# C128toSCART_SMT_V2_2021-01-28.net
KiCad netlist of a schematic drawn in EasyEDA
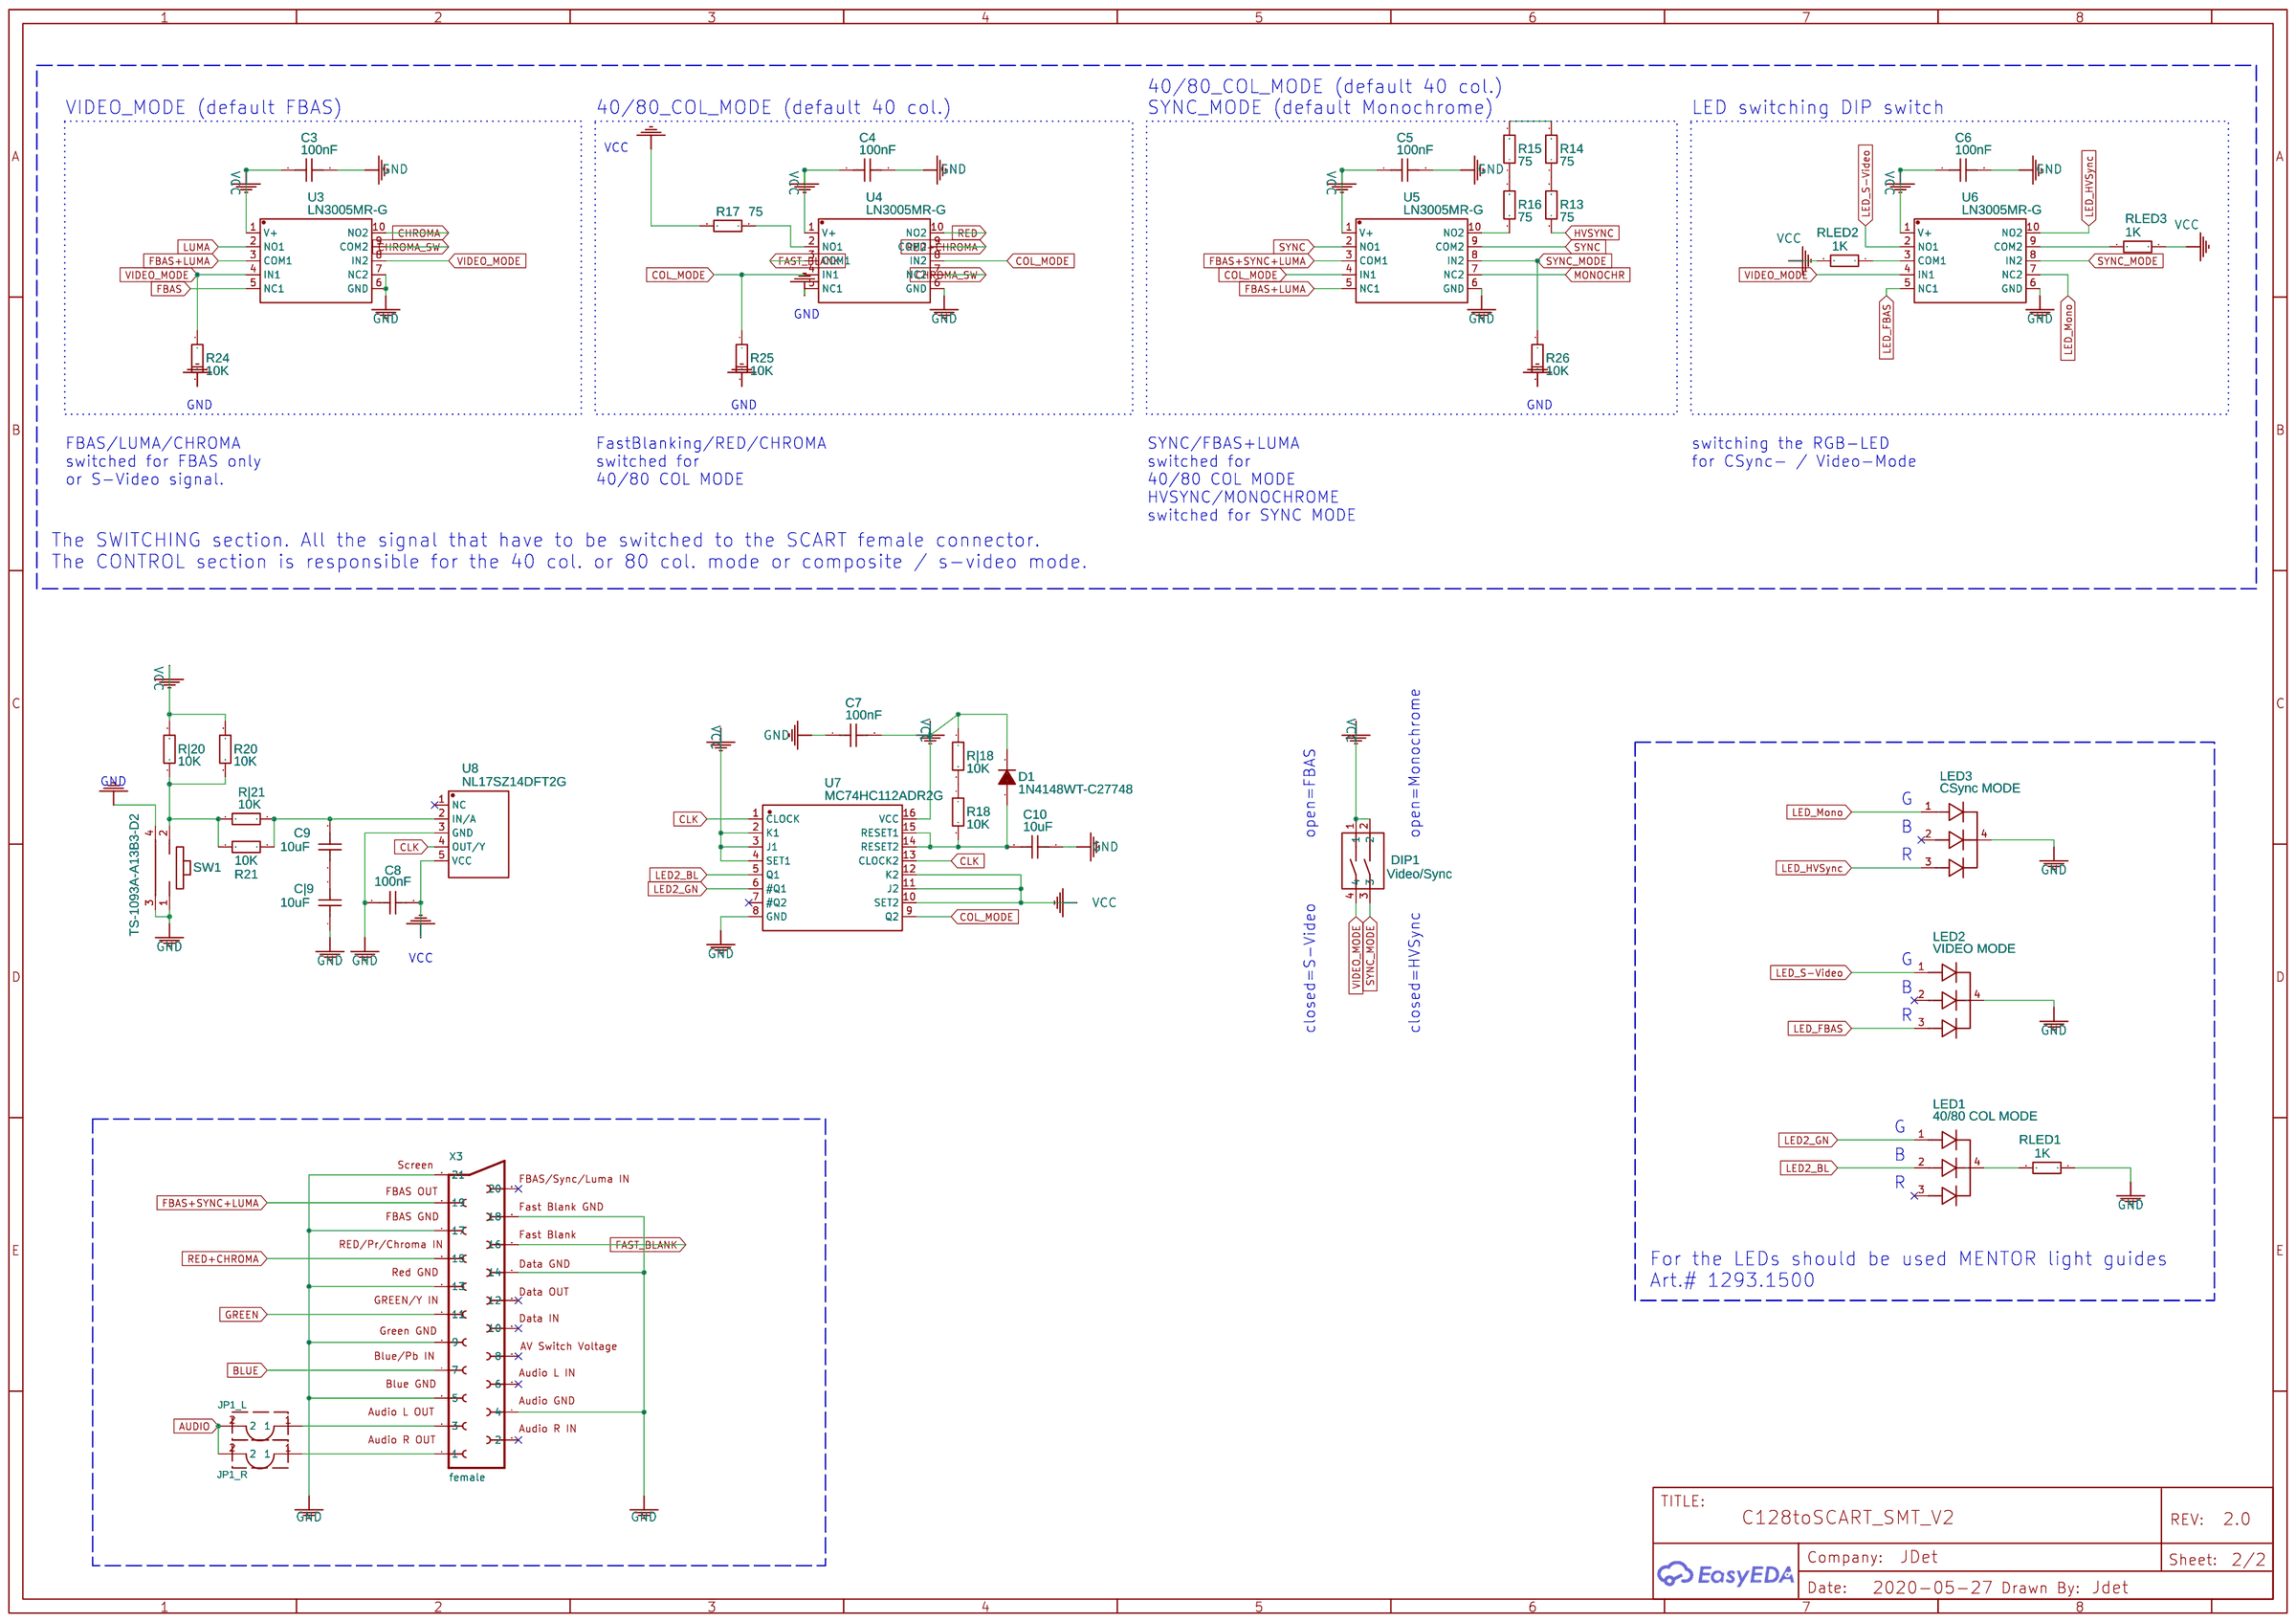
[diagram p0: C128toSCART_SMT_V2#2]
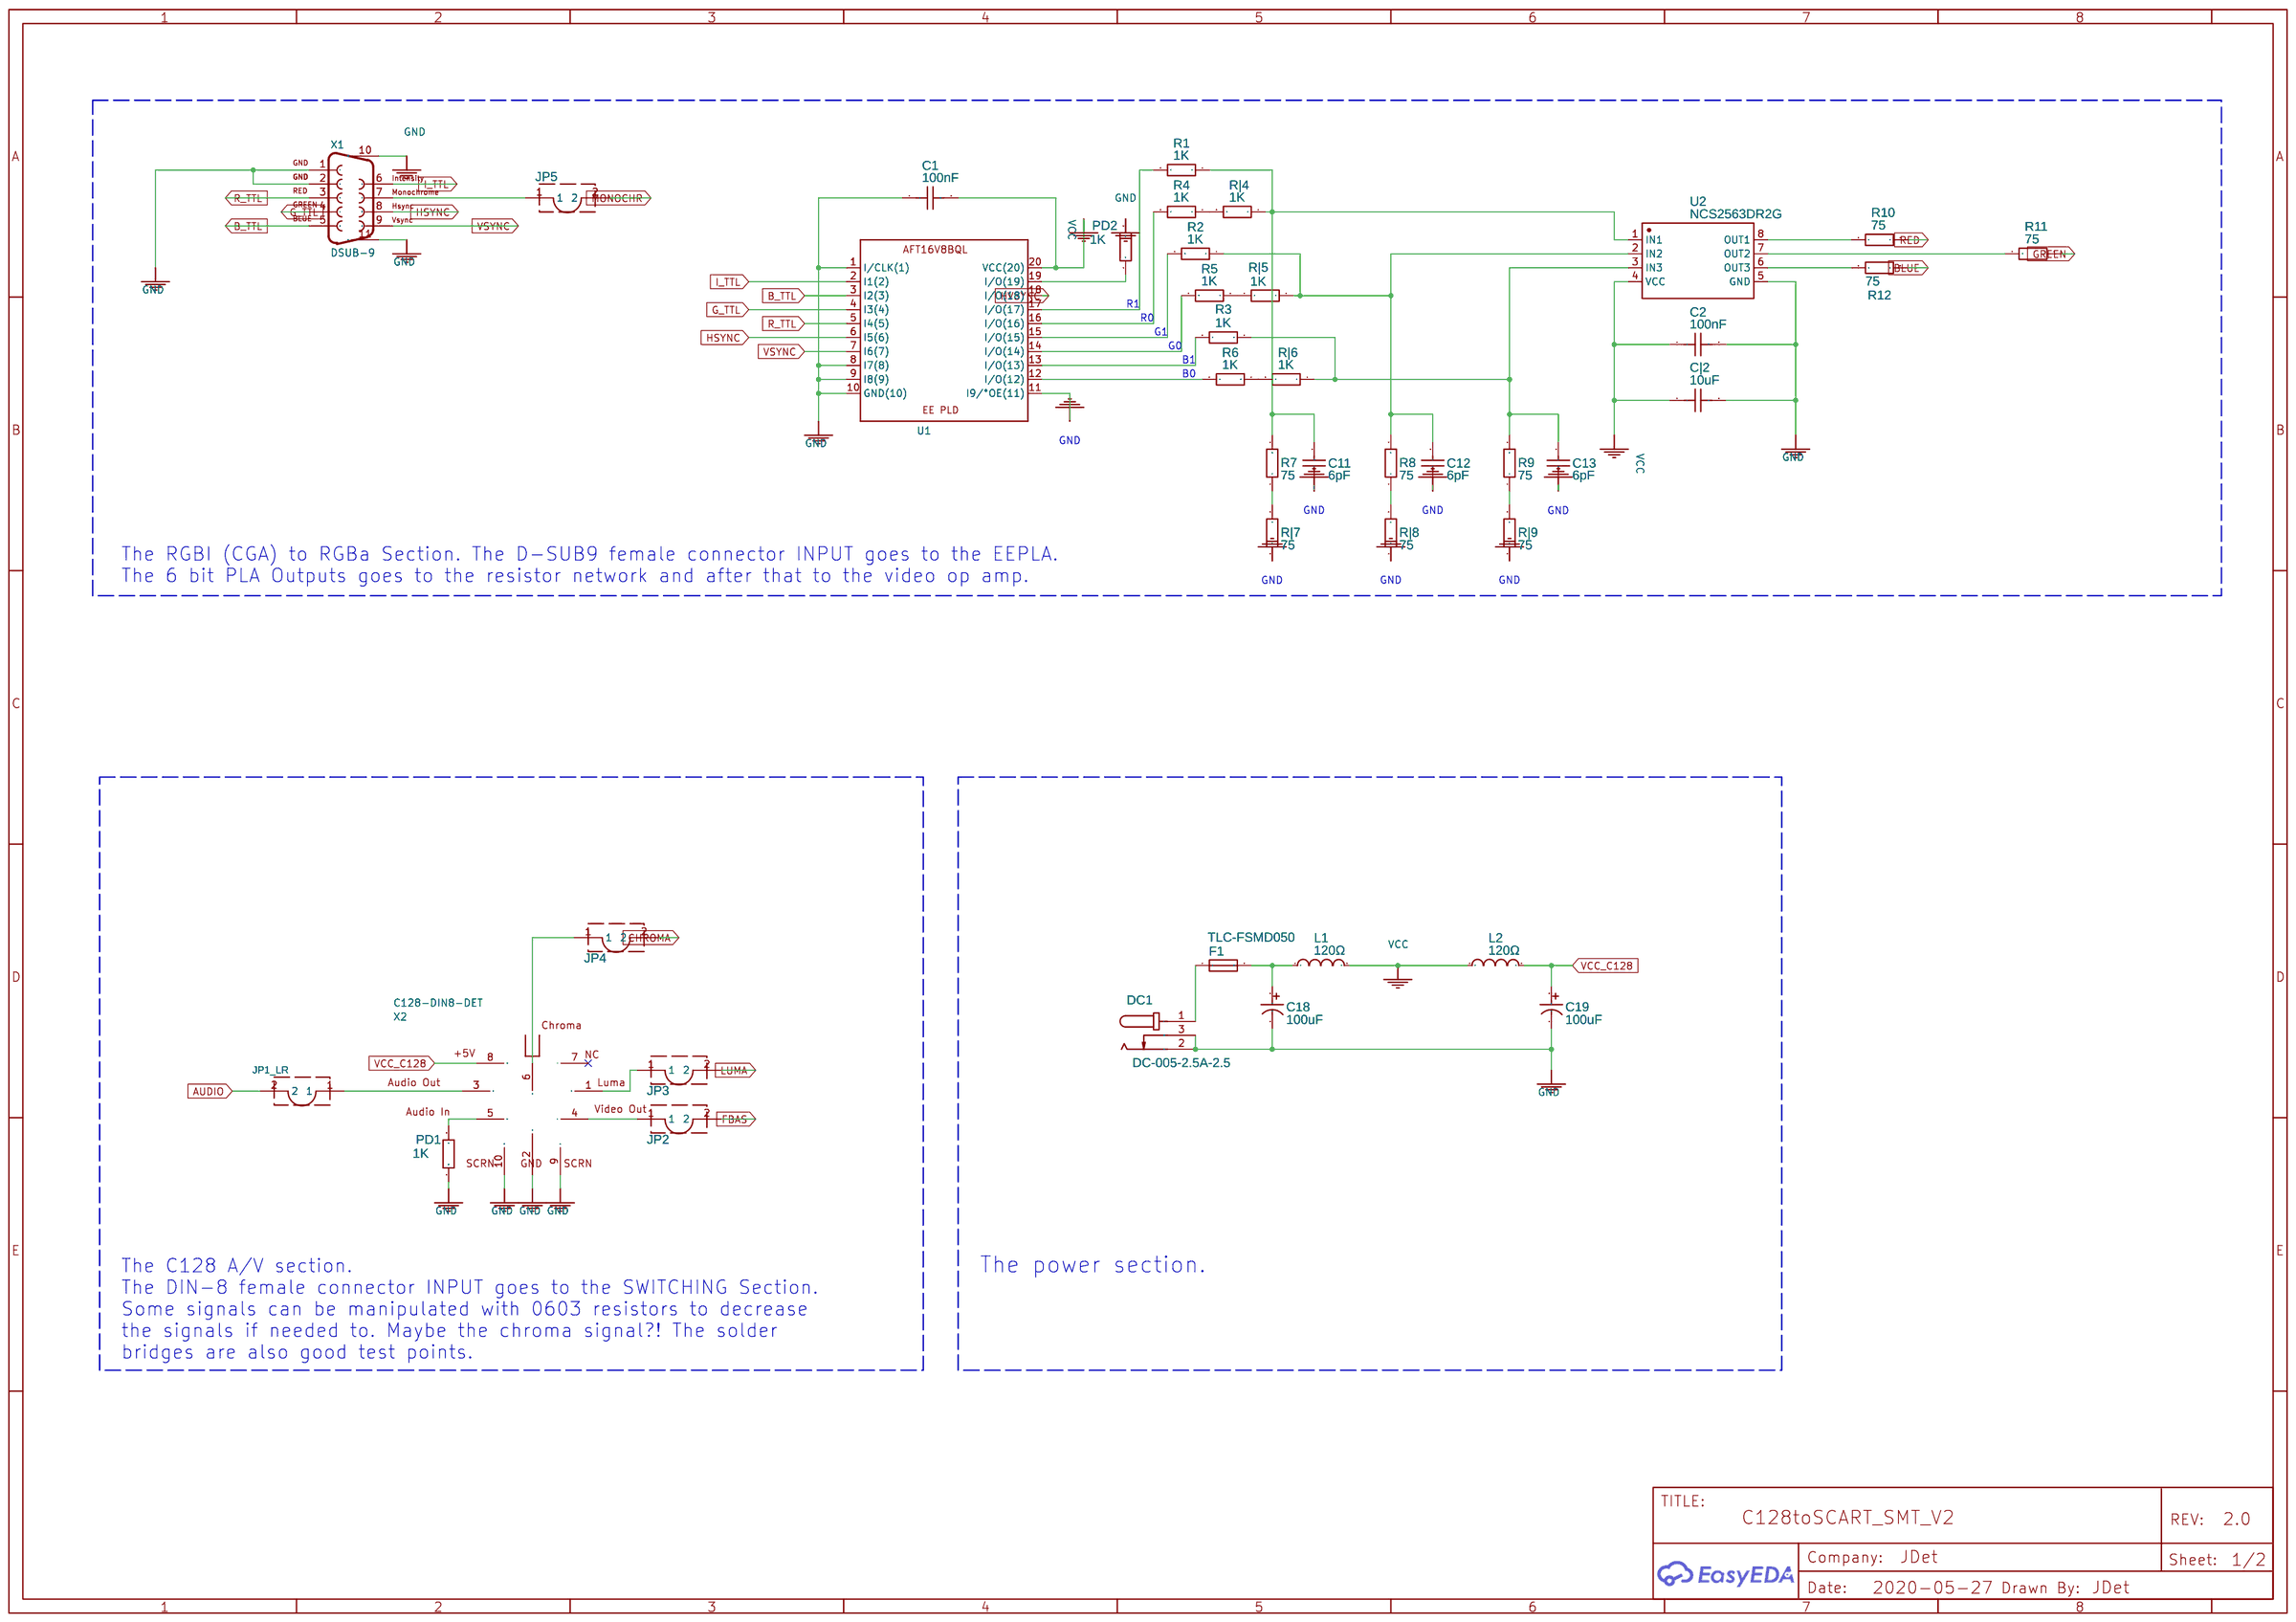
[diagram p1: C128toSCART_SMT_V2#1]

(export (version "E")
  (design (tool "Eeschema 10.0.6"))
  (components
    (comp (ref "C3")
      (value "100nF")
      (fields
        (field (name "BOM_Manufacturer Part") "CC0603KRX7R9BB104")
        (field (name "BOM_Supplier Part") "C14663")
      )
      (libsource (lib "") (part "CC0603KRX7R9BB104"))
    )
    (comp (ref "C4")
      (value "100nF")
      (fields
        (field (name "BOM_Manufacturer Part") "CC0603KRX7R9BB104")
        (field (name "BOM_Supplier Part") "C14663")
      )
      (libsource (lib "") (part "CC0603KRX7R9BB104"))
    )
    (comp (ref "C5")
      (value "100nF")
      (fields
        (field (name "BOM_Manufacturer Part") "CC0603KRX7R9BB104")
        (field (name "BOM_Supplier Part") "C14663")
      )
      (libsource (lib "") (part "CC0603KRX7R9BB104"))
    )
    (comp (ref "C6")
      (value "100nF")
      (fields
        (field (name "BOM_Manufacturer Part") "CC0603KRX7R9BB104")
        (field (name "BOM_Supplier Part") "C14663")
      )
      (libsource (lib "") (part "CC0603KRX7R9BB104"))
    )
    (comp (ref "C7")
      (value "100nF")
      (fields
        (field (name "BOM_Manufacturer Part") "CC0603KRX7R9BB104")
        (field (name "BOM_Supplier Part") "C14663")
      )
      (libsource (lib "") (part "CC0603KRX7R9BB104"))
    )
    (comp (ref "C8")
      (value "100nF")
      (fields
        (field (name "BOM_Manufacturer Part") "CC0603KRX7R9BB104")
        (field (name "BOM_Supplier Part") "C14663")
      )
      (libsource (lib "") (part "CC0603KRX7R9BB104"))
    )
    (comp (ref "C9")
      (value "10uF")
      (fields
        (field (name "BOM_Manufacturer Part") "CL10A106KP8NNNC")
        (field (name "BOM_Supplier Part") "C19702")
      )
      (libsource (lib "") (part "CL10A106KP8NNNC_1"))
    )
    (comp (ref "C10")
      (value "10uF")
      (fields
        (field (name "BOM_Manufacturer Part") "CL10A106KP8NNNC")
        (field (name "BOM_Supplier Part") "C19702")
      )
      (libsource (lib "") (part "CL10A106KP8NNNC_2"))
    )
    (comp (ref "C|9")
      (value "10uF")
      (fields
        (field (name "BOM_Manufacturer Part") "CL10A106KP8NNNC")
        (field (name "BOM_Supplier Part") "C19702")
      )
      (libsource (lib "") (part "CL10A106KP8NNNC"))
    )
    (comp (ref "D1")
      (value "1N4148WT-C27748")
      (fields (field (name "BOM_Manufacturer Part") "1N4148WT") (field (name "BOM_Supplier Part") "C27748"))
      (libsource (lib "") (part "1N4148WT-C27748"))
    )
    (comp (ref "DIP1")
      (value "Video/Sync")
      (fields (field (name "BOM_Manufacturer Part") "HAD-02HWA-R") (field (name "BOM_Supplier Part") "C4669"))
      (libsource (lib "") (part "HAD-02HWA-R"))
    )
    (comp (ref "JP1_L") (value "JUMPER_CLOSED") (libsource (lib "") (part "JUMPER_CLOSED_1")))
    (comp (ref "JP1_R") (value "JUMPER_CLOSED") (libsource (lib "") (part "JUMPER_CLOSED")))
    (comp (ref "LED1")
      (value "40/80 COL MODE")
      (fields
        (field (name "BOM_Manufacturer Part") "TJ-S1615SW6TGLCCSRGB-A5")
        (field (name "BOM_Supplier Part") "C273611")
      )
      (libsource (lib "") (part "TJ-S1615SW6TGLCCSRGB-A5"))
    )
    (comp (ref "LED2")
      (value "VIDEO MODE")
      (fields
        (field (name "BOM_Manufacturer Part") "TJ-S1615SW6TGLCCSRGB-A5")
        (field (name "BOM_Supplier Part") "C273611")
      )
      (libsource (lib "") (part "TJ-S1615SW6TGLCCSRGB-A5"))
    )
    (comp (ref "LED3")
      (value "CSync MODE")
      (fields
        (field (name "BOM_Manufacturer Part") "TJ-S1615SW6TGLCCSRGB-A5")
        (field (name "BOM_Supplier Part") "C273611")
      )
      (libsource (lib "") (part "TJ-S1615SW6TGLCCSRGB-A5"))
    )
    (comp (ref "R13")
      (value "75")
      (fields
        (field (name "BOM_Manufacturer Part") "TC0325B750JT5E")
        (field (name "BOM_Supplier Part") "C146567")
      )
      (libsource (lib "") (part "TC0325B750JT5E"))
    )
    (comp (ref "R14")
      (value "75")
      (fields
        (field (name "BOM_Manufacturer Part") "TC0325B750JT5E")
        (field (name "BOM_Supplier Part") "C146567")
      )
      (libsource (lib "") (part "TC0325B750JT5E"))
    )
    (comp (ref "R15")
      (value "75")
      (fields
        (field (name "BOM_Manufacturer Part") "TC0325B750JT5E")
        (field (name "BOM_Supplier Part") "C146567")
      )
      (libsource (lib "") (part "TC0325B750JT5E"))
    )
    (comp (ref "R16")
      (value "75")
      (fields
        (field (name "BOM_Manufacturer Part") "TC0325B750JT5E")
        (field (name "BOM_Supplier Part") "C146567")
      )
      (libsource (lib "") (part "TC0325B750JT5E"))
    )
    (comp (ref "R17")
      (value "75")
      (fields
        (field (name "BOM_Manufacturer Part") "TC0325B750JT5E")
        (field (name "BOM_Supplier Part") "C146567")
      )
      (libsource (lib "") (part "TC0325B750JT5E_1"))
    )
    (comp (ref "R18")
      (value "10K")
      (fields
        (field (name "BOM_Manufacturer Part") "TC0310B1002T5E")
        (field (name "BOM_Supplier Part") "C190321")
      )
      (libsource (lib "") (part "TC0310B1002T5E_1"))
    )
    (comp (ref "R20")
      (value "10K")
      (fields
        (field (name "BOM_Manufacturer Part") "TC0310B1002T5E")
        (field (name "BOM_Supplier Part") "C190321")
      )
      (libsource (lib "") (part "TC0310B1002T5E_2"))
    )
    (comp (ref "R21")
      (value "10K")
      (fields
        (field (name "BOM_Manufacturer Part") "TC0310B1002T5E")
        (field (name "BOM_Supplier Part") "C190321")
      )
      (libsource (lib "") (part "TC0310B1002T5E"))
    )
    (comp (ref "R24")
      (value "10K")
      (fields
        (field (name "BOM_Manufacturer Part") "TC0310B1002T5E")
        (field (name "BOM_Supplier Part") "C190321")
      )
      (libsource (lib "") (part "TC0310B1002T5E_1"))
    )
    (comp (ref "R25")
      (value "10K")
      (fields
        (field (name "BOM_Manufacturer Part") "TC0310B1002T5E")
        (field (name "BOM_Supplier Part") "C190321")
      )
      (libsource (lib "") (part "TC0310B1002T5E_1"))
    )
    (comp (ref "R26")
      (value "10K")
      (fields
        (field (name "BOM_Manufacturer Part") "TC0310B1002T5E")
        (field (name "BOM_Supplier Part") "C190321")
      )
      (libsource (lib "") (part "TC0310B1002T5E_1"))
    )
    (comp (ref "RLED1")
      (value "1K")
      (fields
        (field (name "BOM_Manufacturer Part") "TC0325F1001T5E")
        (field (name "BOM_Supplier Part") "C128783")
      )
      (libsource (lib "") (part "TC0325F1001T5E"))
    )
    (comp (ref "RLED2")
      (value "1K")
      (fields
        (field (name "BOM_Manufacturer Part") "TC0325F1001T5E")
        (field (name "BOM_Supplier Part") "C128783")
      )
      (libsource (lib "") (part "TC0325F1001T5E"))
    )
    (comp (ref "RLED3")
      (value "1K")
      (fields
        (field (name "BOM_Manufacturer Part") "TC0325F1001T5E")
        (field (name "BOM_Supplier Part") "C128783")
      )
      (libsource (lib "") (part "TC0325F1001T5E"))
    )
    (comp (ref "R|18")
      (value "10K")
      (fields
        (field (name "BOM_Manufacturer Part") "TC0310B1002T5E")
        (field (name "BOM_Supplier Part") "C190321")
      )
      (libsource (lib "") (part "TC0310B1002T5E_5"))
    )
    (comp (ref "R|20")
      (value "10K")
      (fields
        (field (name "BOM_Manufacturer Part") "TC0310B1002T5E")
        (field (name "BOM_Supplier Part") "C190321")
      )
      (libsource (lib "") (part "TC0310B1002T5E_3"))
    )
    (comp (ref "R|21")
      (value "10K")
      (fields
        (field (name "BOM_Manufacturer Part") "TC0310B1002T5E")
        (field (name "BOM_Supplier Part") "C190321")
      )
      (libsource (lib "") (part "TC0310B1002T5E_4"))
    )
    (comp (ref "SW1")
      (value "TS-1093A-A13B3-D2")
      (fields (field (name "BOM_Supplier Part") "C499320"))
      (libsource (lib "") (part "TS-1093A-A13B3-D2"))
    )
    (comp (ref "U3")
      (value "LN3005MR-G")
      (fields (field (name "BOM_Supplier Part") "C236380"))
      (libsource (lib "") (part "LN3005MR-G"))
    )
    (comp (ref "U4")
      (value "LN3005MR-G")
      (fields (field (name "BOM_Supplier Part") "C236380"))
      (libsource (lib "") (part "LN3005MR-G"))
    )
    (comp (ref "U5")
      (value "LN3005MR-G")
      (fields (field (name "BOM_Supplier Part") "C236380"))
      (libsource (lib "") (part "LN3005MR-G"))
    )
    (comp (ref "U6")
      (value "LN3005MR-G")
      (fields (field (name "BOM_Supplier Part") "C236380"))
      (libsource (lib "") (part "LN3005MR-G"))
    )
    (comp (ref "U7")
      (value "MC74HC112ADR2G")
      (fields (field (name "BOM_Supplier Part") "C233600"))
      (libsource (lib "") (part "MC74HC112ADR2G"))
    )
    (comp (ref "U8")
      (value "NL17SZ14DFT2G")
      (fields (field (name "BOM_Supplier Part") "C113256"))
      (libsource (lib "") (part "NL17SZ14DFT2G"))
    )
    (comp (ref "X3") (value "female") (libsource (lib "") (part "Unknown_325_-200")))
    (comp (ref "C1")
      (value "100nF")
      (fields
        (field (name "BOM_Manufacturer Part") "CC0603KRX7R9BB104")
        (field (name "BOM_Supplier Part") "C14663")
      )
      (libsource (lib "") (part "CC0603KRX7R9BB104"))
    )
    (comp (ref "C2")
      (value "100nF")
      (fields
        (field (name "BOM_Manufacturer Part") "CC0603KRX7R9BB104")
        (field (name "BOM_Supplier Part") "C14663")
      )
      (libsource (lib "") (part "CC0603KRX7R9BB104"))
    )
    (comp (ref "C11")
      (value "6pF")
      (fields
        (field (name "BOM_Manufacturer Part") "0603CG6R0C500NT")
        (field (name "BOM_Supplier Part") "C37474")
      )
      (libsource (lib "") (part "0603CG6R0C500NT"))
    )
    (comp (ref "C12")
      (value "6pF")
      (fields
        (field (name "BOM_Manufacturer Part") "0603CG6R0C500NT")
        (field (name "BOM_Supplier Part") "C37474")
      )
      (libsource (lib "") (part "0603CG6R0C500NT"))
    )
    (comp (ref "C13")
      (value "6pF")
      (fields
        (field (name "BOM_Manufacturer Part") "0603CG6R0C500NT")
        (field (name "BOM_Supplier Part") "C37474")
      )
      (libsource (lib "") (part "0603CG6R0C500NT"))
    )
    (comp (ref "C18")
      (value "100uF")
      (fields
        (field (name "BOM_Manufacturer Part") "VZS101M1ATR-0506")
        (field (name "BOM_Supplier Part") "C140924")
      )
      (libsource (lib "") (part "VZS101M1ATR-0506"))
    )
    (comp (ref "C19")
      (value "100uF")
      (fields
        (field (name "BOM_Manufacturer Part") "VZS101M1ATR-0506")
        (field (name "BOM_Supplier Part") "C140924")
      )
      (libsource (lib "") (part "VZS101M1ATR-0506"))
    )
    (comp (ref "C|2")
      (value "10uF")
      (fields
        (field (name "BOM_Manufacturer Part") "CL10A106KP8NNNC")
        (field (name "BOM_Supplier Part") "C19702")
      )
      (libsource (lib "") (part "CL10A106KP8NNNC"))
    )
    (comp (ref "DC1")
      (value "DC-005-2.5A-2.5")
      (fields (field (name "BOM_Supplier Part") "C319098"))
      (libsource (lib "") (part "DC-005-2.5A-2.5"))
    )
    (comp (ref "F1")
      (value "TLC-FSMD050")
      (fields (field (name "BOM_Supplier Part") "C261937"))
      (libsource (lib "") (part "TLC-FSMD050"))
    )
    (comp (ref "JP1_LR") (value "JUMPER_CLOSED") (libsource (lib "") (part "JUMPER_CLOSED_1")))
    (comp (ref "JP2") (value "JUMPER_CLOSED") (libsource (lib "") (part "JUMPER_CLOSED")))
    (comp (ref "JP3") (value "JUMPER_CLOSED") (libsource (lib "") (part "JUMPER_CLOSED")))
    (comp (ref "JP4") (value "JUMPER_CLOSED") (libsource (lib "") (part "JUMPER_CLOSED")))
    (comp (ref "JP5") (value "JUMPER_CLOSED") (libsource (lib "") (part "JUMPER_CLOSED")))
    (comp (ref "L1")
      (value "120Ω")
      (fields
        (field (name "BOM_Manufacturer Part") "GZ1608D121TF")
        (field (name "BOM_Supplier Part") "C18527")
      )
      (libsource (lib "") (part "GZ1608D121TF"))
    )
    (comp (ref "L2")
      (value "120Ω")
      (fields
        (field (name "BOM_Manufacturer Part") "GZ1608D121TF")
        (field (name "BOM_Supplier Part") "C18527")
      )
      (libsource (lib "") (part "GZ1608D121TF_1"))
    )
    (comp (ref "PD1")
      (value "1K")
      (fields
        (field (name "BOM_Manufacturer Part") "TC0325F1001T5E")
        (field (name "BOM_Supplier Part") "C128783")
      )
      (libsource (lib "") (part "TC0325F1001T5E"))
    )
    (comp (ref "PD2")
      (value "1K")
      (fields
        (field (name "BOM_Manufacturer Part") "TC0325F1001T5E")
        (field (name "BOM_Supplier Part") "C128783")
      )
      (libsource (lib "") (part "TC0325F1001T5E"))
    )
    (comp (ref "R1")
      (value "1K")
      (fields
        (field (name "BOM_Manufacturer Part") "TC0325F1001T5E")
        (field (name "BOM_Supplier Part") "C128783")
      )
      (libsource (lib "") (part "TC0325F1001T5E_1"))
    )
    (comp (ref "R2")
      (value "1K")
      (fields
        (field (name "BOM_Manufacturer Part") "TC0325F1001T5E")
        (field (name "BOM_Supplier Part") "C128783")
      )
      (libsource (lib "") (part "TC0325F1001T5E_1"))
    )
    (comp (ref "R3")
      (value "1K")
      (fields
        (field (name "BOM_Manufacturer Part") "TC0325F1001T5E")
        (field (name "BOM_Supplier Part") "C128783")
      )
      (libsource (lib "") (part "TC0325F1001T5E_1"))
    )
    (comp (ref "R4")
      (value "1K")
      (fields
        (field (name "BOM_Manufacturer Part") "TC0325F1001T5E")
        (field (name "BOM_Supplier Part") "C128783")
      )
      (libsource (lib "") (part "TC0325F1001T5E_1"))
    )
    (comp (ref "R5")
      (value "1K")
      (fields
        (field (name "BOM_Manufacturer Part") "TC0325F1001T5E")
        (field (name "BOM_Supplier Part") "C128783")
      )
      (libsource (lib "") (part "TC0325F1001T5E_1"))
    )
    (comp (ref "R6")
      (value "1K")
      (fields
        (field (name "BOM_Manufacturer Part") "TC0325F1001T5E")
        (field (name "BOM_Supplier Part") "C128783")
      )
      (libsource (lib "") (part "TC0325F1001T5E_1"))
    )
    (comp (ref "R7")
      (value "75")
      (fields
        (field (name "BOM_Manufacturer Part") "TC0325B750JT5E")
        (field (name "BOM_Supplier Part") "C146567")
      )
      (libsource (lib "") (part "TC0325B750JT5E"))
    )
    (comp (ref "R8")
      (value "75")
      (fields
        (field (name "BOM_Manufacturer Part") "TC0325B750JT5E")
        (field (name "BOM_Supplier Part") "C146567")
      )
      (libsource (lib "") (part "TC0325B750JT5E"))
    )
    (comp (ref "R9")
      (value "75")
      (fields
        (field (name "BOM_Manufacturer Part") "TC0325B750JT5E")
        (field (name "BOM_Supplier Part") "C146567")
      )
      (libsource (lib "") (part "TC0325B750JT5E"))
    )
    (comp (ref "R10")
      (value "75")
      (fields
        (field (name "BOM_Manufacturer Part") "TC0325B750JT5E")
        (field (name "BOM_Supplier Part") "C146567")
      )
      (libsource (lib "") (part "TC0325B750JT5E_2"))
    )
    (comp (ref "R11")
      (value "75")
      (fields
        (field (name "BOM_Manufacturer Part") "TC0325B750JT5E")
        (field (name "BOM_Supplier Part") "C146567")
      )
      (libsource (lib "") (part "TC0325B750JT5E_2"))
    )
    (comp (ref "R12")
      (value "75")
      (fields
        (field (name "BOM_Manufacturer Part") "TC0325B750JT5E")
        (field (name "BOM_Supplier Part") "C146567")
      )
      (libsource (lib "") (part "TC0325B750JT5E_2"))
    )
    (comp (ref "R|4")
      (value "1K")
      (fields
        (field (name "BOM_Manufacturer Part") "TC0325F1001T5E")
        (field (name "BOM_Supplier Part") "C128783")
      )
      (libsource (lib "") (part "TC0325F1001T5E_2"))
    )
    (comp (ref "R|5")
      (value "1K")
      (fields
        (field (name "BOM_Manufacturer Part") "TC0325F1001T5E")
        (field (name "BOM_Supplier Part") "C128783")
      )
      (libsource (lib "") (part "TC0325F1001T5E_2"))
    )
    (comp (ref "R|6")
      (value "1K")
      (fields
        (field (name "BOM_Manufacturer Part") "TC0325F1001T5E")
        (field (name "BOM_Supplier Part") "C128783")
      )
      (libsource (lib "") (part "TC0325F1001T5E_2"))
    )
    (comp (ref "R|7")
      (value "75")
      (fields
        (field (name "BOM_Manufacturer Part") "TC0325B750JT5E")
        (field (name "BOM_Supplier Part") "C146567")
      )
      (libsource (lib "") (part "TC0325B750JT5E_1"))
    )
    (comp (ref "R|8")
      (value "75")
      (fields
        (field (name "BOM_Manufacturer Part") "TC0325B750JT5E")
        (field (name "BOM_Supplier Part") "C146567")
      )
      (libsource (lib "") (part "TC0325B750JT5E_1"))
    )
    (comp (ref "R|9")
      (value "75")
      (fields
        (field (name "BOM_Manufacturer Part") "TC0325B750JT5E")
        (field (name "BOM_Supplier Part") "C146567")
      )
      (libsource (lib "") (part "TC0325B750JT5E_1"))
    )
    (comp (ref "U1") (value "ATF16V8BQ") (libsource (lib "") (part "Unknown_650_-880")))
    (comp (ref "U2")
      (value "NCS2563DR2G")
      (fields (field (name "BOM_Supplier Part") "C97773"))
      (libsource (lib "") (part "NCS2563DR2G"))
    )
    (comp (ref "X1") (value "DSUB-9") (libsource (lib "") (part "Unknown_235_-1000")))
    (comp (ref "X2") (value "C128-DIN8-DET") (libsource (lib "") (part "Unknown_365_-360")))
  )
  (nets
    (net (code "1") (name "AUDIO") (class "Default")
      (node (ref "JP1_L") (pin "2") (pinfunction "2_2") (pintype "unspecified"))
      (node (ref "JP1_LR") (pin "2") (pinfunction "2_2") (pintype "unspecified"))
      (node (ref "JP1_R") (pin "2") (pinfunction "2_2") (pintype "unspecified"))
    )
    (net (code "2") (name "BLUE") (class "Default")
      (node (ref "R12") (pin "1") (pinfunction "1_1") (pintype "input"))
      (node (ref "X3") (pin "7") (pinfunction "7_7") (pintype "bidirectional"))
    )
    (net (code "3") (name "B_TTL") (class "Default")
      (node (ref "U1") (pin "3") (pinfunction "I2(3)_3") (pintype "bidirectional"))
      (node (ref "X1") (pin "5") (pinfunction "5_5") (pintype "bidirectional"))
    )
    (net (code "4") (name "CHROMA") (class "Default")
      (node (ref "JP4") (pin "2") (pinfunction "2_2") (pintype "unspecified"))
      (node (ref "U3") (pin "10") (pinfunction "NO2_10") (pintype "unspecified"))
    )
    (net (code "5") (name "CHROMA_SW") (class "Default")
      (node (ref "U3") (pin "9") (pinfunction "COM2_9") (pintype "unspecified"))
      (node (ref "U4") (pin "7") (pinfunction "NC2_7") (pintype "unspecified"))
    )
    (net (code "6") (name "CLK") (class "Default")
      (node (ref "U7") (pin "1") (pinfunction "CLOCK_1") (pintype "unspecified"))
      (node (ref "U7") (pin "13") (pinfunction "CLOCK2_13") (pintype "unspecified"))
      (node (ref "U8") (pin "4") (pinfunction "OUT/Y_4") (pintype "unspecified"))
    )
    (net (code "7") (name "COL_MODE") (class "Default")
      (node (ref "R25") (pin "1") (pinfunction "1_1") (pintype "unspecified"))
      (node (ref "U4") (pin "4") (pinfunction "IN1_4") (pintype "unspecified"))
      (node (ref "U4") (pin "8") (pinfunction "IN2_8") (pintype "unspecified"))
      (node (ref "U5") (pin "4") (pinfunction "IN1_4") (pintype "unspecified"))
      (node (ref "U7") (pin "9") (pinfunction "Q2_9") (pintype "unspecified"))
    )
    (net (code "8") (name "FAST_BLANK") (class "Default")
      (node (ref "U4") (pin "3") (pinfunction "COM1_3") (pintype "unspecified"))
      (node (ref "X3") (pin "16") (pinfunction "16_16") (pintype "bidirectional"))
    )
    (net (code "9") (name "FBAS") (class "Default")
      (node (ref "JP2") (pin "2") (pinfunction "2_2") (pintype "unspecified"))
      (node (ref "U3") (pin "5") (pinfunction "NC1_5") (pintype "unspecified"))
    )
    (net (code "10") (name "FBAS+LUMA") (class "Default")
      (node (ref "U3") (pin "3") (pinfunction "COM1_3") (pintype "unspecified"))
      (node (ref "U5") (pin "5") (pinfunction "NC1_5") (pintype "unspecified"))
    )
    (net (code "11") (name "FBAS+SYNC+LUMA") (class "Default")
      (node (ref "U5") (pin "3") (pinfunction "COM1_3") (pintype "unspecified"))
      (node (ref "X3") (pin "19") (pinfunction "19_19") (pintype "bidirectional"))
    )
    (net (code "12") (name "GND") (class "Default")
      (node (ref "C1") (pin "1") (pinfunction "1_1") (pintype "unspecified"))
      (node (ref "C10") (pin "1") (pinfunction "1_1") (pintype "unspecified"))
      (node (ref "C11") (pin "1") (pinfunction "1_1") (pintype "input"))
      (node (ref "C12") (pin "1") (pinfunction "1_1") (pintype "input"))
      (node (ref "C13") (pin "1") (pinfunction "1_1") (pintype "input"))
      (node (ref "C18") (pin "2") (pinfunction "2_2") (pintype "input"))
      (node (ref "C19") (pin "2") (pinfunction "2_2") (pintype "input"))
      (node (ref "C2") (pin "2") (pinfunction "2_2") (pintype "unspecified"))
      (node (ref "C3") (pin "2") (pinfunction "2_2") (pintype "unspecified"))
      (node (ref "C4") (pin "2") (pinfunction "2_2") (pintype "unspecified"))
      (node (ref "C5") (pin "2") (pinfunction "2_2") (pintype "unspecified"))
      (node (ref "C6") (pin "2") (pinfunction "2_2") (pintype "unspecified"))
      (node (ref "C7") (pin "1") (pinfunction "1_1") (pintype "unspecified"))
      (node (ref "C8") (pin "1") (pinfunction "1_1") (pintype "unspecified"))
      (node (ref "C|2") (pin "2") (pinfunction "2_2") (pintype "unspecified"))
      (node (ref "C|9") (pin "1") (pinfunction "1_1") (pintype "unspecified"))
      (node (ref "DC1") (pin "2") (pinfunction "2_2") (pintype "unspecified"))
      (node (ref "DC1") (pin "3") (pinfunction "3_3") (pintype "unspecified"))
      (node (ref "LED2") (pin "4") (pinfunction "4_4") (pintype "unspecified"))
      (node (ref "LED3") (pin "4") (pinfunction "4_4") (pintype "unspecified"))
      (node (ref "PD1") (pin "1") (pinfunction "1_1") (pintype "unspecified"))
      (node (ref "PD2") (pin "2") (pinfunction "2_2") (pintype "unspecified"))
      (node (ref "R24") (pin "2") (pinfunction "2_2") (pintype "unspecified"))
      (node (ref "R25") (pin "2") (pinfunction "2_2") (pintype "unspecified"))
      (node (ref "R26") (pin "2") (pinfunction "2_2") (pintype "unspecified"))
      (node (ref "RLED1") (pin "1") (pinfunction "1_1") (pintype "unspecified"))
      (node (ref "R|7") (pin "1") (pinfunction "1_1") (pintype "input"))
      (node (ref "R|8") (pin "1") (pinfunction "1_1") (pintype "input"))
      (node (ref "R|9") (pin "1") (pinfunction "1_1") (pintype "input"))
      (node (ref "SW1") (pin "1") (pinfunction "1_1") (pintype "unspecified"))
      (node (ref "SW1") (pin "3") (pinfunction "3_3") (pintype "unspecified"))
      (node (ref "SW1") (pin "4") (pinfunction "4_4") (pintype "unspecified"))
      (node (ref "U1") (pin "1") (pinfunction "I/CLK(1)_1") (pintype "bidirectional"))
      (node (ref "U1") (pin "10") (pinfunction "GND(10)_10") (pintype "bidirectional"))
      (node (ref "U1") (pin "11") (pinfunction "I9/°OE(11)_11") (pintype "bidirectional"))
      (node (ref "U1") (pin "8") (pinfunction "I7(8)_8") (pintype "bidirectional"))
      (node (ref "U1") (pin "9") (pinfunction "I8(9)_9") (pintype "bidirectional"))
      (node (ref "U2") (pin "5") (pinfunction "GND_5") (pintype "unspecified"))
      (node (ref "U3") (pin "6") (pinfunction "GND_6") (pintype "unspecified"))
      (node (ref "U3") (pin "7") (pinfunction "NC2_7") (pintype "unspecified"))
      (node (ref "U4") (pin "5") (pinfunction "NC1_5") (pintype "unspecified"))
      (node (ref "U4") (pin "6") (pinfunction "GND_6") (pintype "unspecified"))
      (node (ref "U5") (pin "6") (pinfunction "GND_6") (pintype "unspecified"))
      (node (ref "U6") (pin "6") (pinfunction "GND_6") (pintype "unspecified"))
      (node (ref "U7") (pin "8") (pinfunction "GND_8") (pintype "unspecified"))
      (node (ref "U8") (pin "3") (pinfunction "GND_3") (pintype "unspecified"))
      (node (ref "X1") (pin "1") (pinfunction "1_1") (pintype "bidirectional"))
      (node (ref "X1") (pin "10") (pinfunction "10_10") (pintype "bidirectional"))
      (node (ref "X1") (pin "11") (pinfunction "11_11") (pintype "bidirectional"))
      (node (ref "X1") (pin "2") (pinfunction "2_2") (pintype "bidirectional"))
      (node (ref "X2") (pin "10") (pinfunction "10_10") (pintype "bidirectional"))
      (node (ref "X2") (pin "2") (pinfunction "2_2") (pintype "bidirectional"))
      (node (ref "X2") (pin "9") (pinfunction "9_9") (pintype "bidirectional"))
      (node (ref "X3") (pin "13") (pinfunction "13_13") (pintype "bidirectional"))
      (node (ref "X3") (pin "14") (pinfunction "14_14") (pintype "bidirectional"))
      (node (ref "X3") (pin "17") (pinfunction "17_17") (pintype "bidirectional"))
      (node (ref "X3") (pin "18") (pinfunction "18_18") (pintype "bidirectional"))
      (node (ref "X3") (pin "21") (pinfunction "21_21") (pintype "bidirectional"))
      (node (ref "X3") (pin "4") (pinfunction "4_4") (pintype "bidirectional"))
      (node (ref "X3") (pin "5") (pinfunction "5_5") (pintype "bidirectional"))
      (node (ref "X3") (pin "9") (pinfunction "9_9") (pintype "bidirectional"))
    )
    (net (code "13") (name "GREEN") (class "Default")
      (node (ref "R11") (pin "1") (pinfunction "1_1") (pintype "input"))
      (node (ref "X3") (pin "11") (pinfunction "11_11") (pintype "bidirectional"))
    )
    (net (code "14") (name "G_TTL") (class "Default")
      (node (ref "U1") (pin "4") (pinfunction "I3(4)_4") (pintype "bidirectional"))
      (node (ref "X1") (pin "4") (pinfunction "4_4") (pintype "bidirectional"))
    )
    (net (code "15") (name "HSYNC") (class "Default")
      (node (ref "U1") (pin "6") (pinfunction "I5(6)_6") (pintype "bidirectional"))
      (node (ref "X1") (pin "8") (pinfunction "8_8") (pintype "bidirectional"))
    )
    (net (code "16") (name "HVSYNC") (class "Default")
      (node (ref "R13") (pin "1") (pinfunction "1_1") (pintype "input"))
      (node (ref "U1") (pin "18") (pinfunction "I/O(18)_18") (pintype "bidirectional"))
    )
    (net (code "17") (name "I_TTL") (class "Default")
      (node (ref "U1") (pin "2") (pinfunction "I1(2)_2") (pintype "bidirectional"))
      (node (ref "X1") (pin "6") (pinfunction "6_6") (pintype "bidirectional"))
    )
    (net (code "18") (name "LED2_BL") (class "Default")
      (node (ref "LED1") (pin "2") (pinfunction "B_2") (pintype "unspecified"))
      (node (ref "U7") (pin "5") (pinfunction "Q1_5") (pintype "unspecified"))
    )
    (net (code "19") (name "LED2_GN") (class "Default")
      (node (ref "LED1") (pin "1") (pinfunction "G_1") (pintype "unspecified"))
      (node (ref "U7") (pin "6") (pinfunction "#Q1_6") (pintype "unspecified"))
    )
    (net (code "20") (name "LED_FBAS") (class "Default")
      (node (ref "LED2") (pin "3") (pinfunction "R_3") (pintype "unspecified"))
      (node (ref "U6") (pin "5") (pinfunction "NC1_5") (pintype "unspecified"))
    )
    (net (code "21") (name "LED_HVSync") (class "Default")
      (node (ref "LED3") (pin "3") (pinfunction "R_3") (pintype "unspecified"))
      (node (ref "U6") (pin "10") (pinfunction "NO2_10") (pintype "unspecified"))
    )
    (net (code "22") (name "LED_Mono") (class "Default")
      (node (ref "LED3") (pin "1") (pinfunction "G_1") (pintype "unspecified"))
      (node (ref "U6") (pin "7") (pinfunction "NC2_7") (pintype "unspecified"))
    )
    (net (code "23") (name "LED_S-Video") (class "Default")
      (node (ref "LED2") (pin "1") (pinfunction "G_1") (pintype "unspecified"))
      (node (ref "U6") (pin "2") (pinfunction "NO1_2") (pintype "unspecified"))
    )
    (net (code "24") (name "LUMA") (class "Default")
      (node (ref "JP3") (pin "2") (pinfunction "2_2") (pintype "unspecified"))
      (node (ref "U3") (pin "2") (pinfunction "NO1_2") (pintype "unspecified"))
    )
    (net (code "25") (name "MONOCHR") (class "Default")
      (node (ref "JP5") (pin "2") (pinfunction "2_2") (pintype "unspecified"))
      (node (ref "U5") (pin "7") (pinfunction "NC2_7") (pintype "unspecified"))
    )
    (net (code "26") (name "Net-(C9-Pad1)") (class "Default")
      (node (ref "C9") (pin "1") (pinfunction "1_1") (pintype "unspecified"))
      (node (ref "C|9") (pin "2") (pinfunction "2_2") (pintype "unspecified"))
    )
    (net (code "27") (name "Net-(C18-Pad1)") (class "Default")
      (node (ref "C18") (pin "1") (pinfunction "1_1") (pintype "input"))
      (node (ref "F1") (pin "2") (pinfunction "2_2") (pintype "unspecified"))
      (node (ref "L1") (pin "1") (pinfunction "1_1") (pintype "unspecified"))
    )
    (net (code "28") (name "Net-(D1-A)") (class "Default")
      (node (ref "C10") (pin "2") (pinfunction "2_2") (pintype "unspecified"))
      (node (ref "D1") (pin "2") (pinfunction "A_2") (pintype "unspecified"))
      (node (ref "R18") (pin "2") (pinfunction "2_2") (pintype "unspecified"))
      (node (ref "U7") (pin "14") (pinfunction "RESET2_14") (pintype "unspecified"))
      (node (ref "U7") (pin "15") (pinfunction "RESET1_15") (pintype "unspecified"))
    )
    (net (code "29") (name "Net-(DC1-Pad1)") (class "Default")
      (node (ref "DC1") (pin "1") (pinfunction "1_1") (pintype "unspecified"))
      (node (ref "F1") (pin "1") (pinfunction "1_1") (pintype "unspecified"))
    )
    (net (code "30") (name "Net-(JP1_L-Pad1)") (class "Default")
      (node (ref "JP1_L") (pin "1") (pinfunction "1_1") (pintype "unspecified"))
      (node (ref "X3") (pin "3") (pinfunction "3_3") (pintype "bidirectional"))
    )
    (net (code "31") (name "Net-(JP1_LR-Pad1)") (class "Default")
      (node (ref "JP1_LR") (pin "1") (pinfunction "1_1") (pintype "unspecified"))
      (node (ref "X2") (pin "3") (pinfunction "3_3") (pintype "bidirectional"))
    )
    (net (code "32") (name "Net-(JP1_R-Pad1)") (class "Default")
      (node (ref "JP1_R") (pin "1") (pinfunction "1_1") (pintype "unspecified"))
      (node (ref "X3") (pin "1") (pinfunction "1_1") (pintype "bidirectional"))
    )
    (net (code "33") (name "Net-(JP2-Pad1)") (class "Default")
      (node (ref "JP2") (pin "1") (pinfunction "1_1") (pintype "unspecified"))
      (node (ref "X2") (pin "4") (pinfunction "4_4") (pintype "bidirectional"))
    )
    (net (code "34") (name "Net-(JP3-Pad1)") (class "Default")
      (node (ref "JP3") (pin "1") (pinfunction "1_1") (pintype "unspecified"))
      (node (ref "X2") (pin "1") (pinfunction "1_1") (pintype "bidirectional"))
    )
    (net (code "35") (name "Net-(JP4-Pad1)") (class "Default")
      (node (ref "JP4") (pin "1") (pinfunction "1_1") (pintype "unspecified"))
      (node (ref "X2") (pin "6") (pinfunction "6_6") (pintype "bidirectional"))
    )
    (net (code "36") (name "Net-(JP5-Pad1)") (class "Default")
      (node (ref "JP5") (pin "1") (pinfunction "1_1") (pintype "unspecified"))
      (node (ref "X1") (pin "7") (pinfunction "7_7") (pintype "bidirectional"))
    )
    (net (code "37") (name "Net-(LED1-Pad4)") (class "Default")
      (node (ref "LED1") (pin "4") (pinfunction "4_4") (pintype "unspecified"))
      (node (ref "RLED1") (pin "2") (pinfunction "2_2") (pintype "unspecified"))
    )
    (net (code "38") (name "Net-(PD1-Pad2)") (class "Default")
      (node (ref "PD1") (pin "2") (pinfunction "2_2") (pintype "unspecified"))
      (node (ref "X2") (pin "5") (pinfunction "5_5") (pintype "bidirectional"))
    )
    (net (code "39") (name "Net-(R4-Pad1)") (class "Default")
      (node (ref "R4") (pin "1") (pinfunction "1_1") (pintype "unspecified"))
      (node (ref "R|4") (pin "2") (pinfunction "2_2") (pintype "unspecified"))
    )
    (net (code "40") (name "Net-(R5-Pad1)") (class "Default")
      (node (ref "R5") (pin "1") (pinfunction "1_1") (pintype "unspecified"))
      (node (ref "R|5") (pin "2") (pinfunction "2_2") (pintype "unspecified"))
    )
    (net (code "41") (name "Net-(R6-Pad1)") (class "Default")
      (node (ref "R6") (pin "1") (pinfunction "1_1") (pintype "unspecified"))
      (node (ref "R|6") (pin "2") (pinfunction "2_2") (pintype "unspecified"))
    )
    (net (code "42") (name "Net-(R7-Pad1)") (class "Default")
      (node (ref "R7") (pin "1") (pinfunction "1_1") (pintype "input"))
      (node (ref "R|7") (pin "2") (pinfunction "2_2") (pintype "input"))
    )
    (net (code "43") (name "Net-(R8-Pad1)") (class "Default")
      (node (ref "R8") (pin "1") (pinfunction "1_1") (pintype "input"))
      (node (ref "R|8") (pin "2") (pinfunction "2_2") (pintype "input"))
    )
    (net (code "44") (name "Net-(R9-Pad1)") (class "Default")
      (node (ref "R9") (pin "1") (pinfunction "1_1") (pintype "input"))
      (node (ref "R|9") (pin "2") (pinfunction "2_2") (pintype "input"))
    )
    (net (code "45") (name "Net-(R13-Pad2)") (class "Default")
      (node (ref "R13") (pin "2") (pinfunction "2_2") (pintype "input"))
      (node (ref "R14") (pin "1") (pinfunction "1_1") (pintype "input"))
    )
    (net (code "46") (name "Net-(R14-Pad2)") (class "Default")
      (node (ref "R14") (pin "2") (pinfunction "2_2") (pintype "input"))
      (node (ref "R15") (pin "2") (pinfunction "2_2") (pintype "input"))
    )
    (net (code "47") (name "Net-(R15-Pad1)") (class "Default")
      (node (ref "R15") (pin "1") (pinfunction "1_1") (pintype "input"))
      (node (ref "R16") (pin "2") (pinfunction "2_2") (pintype "input"))
    )
    (net (code "48") (name "Net-(R18-Pad1)") (class "Default")
      (node (ref "R18") (pin "1") (pinfunction "1_1") (pintype "unspecified"))
      (node (ref "R|18") (pin "2") (pinfunction "2_2") (pintype "unspecified"))
    )
    (net (code "49") (name "Net-(R20-Pad1)") (class "Default")
      (node (ref "R20") (pin "1") (pinfunction "1_1") (pintype "unspecified"))
      (node (ref "R21") (pin "2") (pinfunction "2_2") (pintype "unspecified"))
      (node (ref "R|20") (pin "1") (pinfunction "1_1") (pintype "unspecified"))
      (node (ref "R|21") (pin "2") (pinfunction "2_2") (pintype "unspecified"))
      (node (ref "SW1") (pin "2") (pinfunction "2_2") (pintype "unspecified"))
    )
    (net (code "50") (name "Net-(U1-I{slash}O(12))") (class "Default")
      (node (ref "R6") (pin "2") (pinfunction "2_2") (pintype "unspecified"))
      (node (ref "U1") (pin "12") (pinfunction "I/O(12)_12") (pintype "bidirectional"))
    )
    (net (code "51") (name "Net-(U1-I{slash}O(13))") (class "Default")
      (node (ref "R3") (pin "2") (pinfunction "2_2") (pintype "unspecified"))
      (node (ref "U1") (pin "13") (pinfunction "I/O(13)_13") (pintype "bidirectional"))
    )
    (net (code "52") (name "Net-(U1-I{slash}O(14))") (class "Default")
      (node (ref "R5") (pin "2") (pinfunction "2_2") (pintype "unspecified"))
      (node (ref "U1") (pin "14") (pinfunction "I/O(14)_14") (pintype "bidirectional"))
    )
    (net (code "53") (name "Net-(U1-I{slash}O(15))") (class "Default")
      (node (ref "R2") (pin "2") (pinfunction "2_2") (pintype "unspecified"))
      (node (ref "U1") (pin "15") (pinfunction "I/O(15)_15") (pintype "bidirectional"))
    )
    (net (code "54") (name "Net-(U1-I{slash}O(16))") (class "Default")
      (node (ref "R4") (pin "2") (pinfunction "2_2") (pintype "unspecified"))
      (node (ref "U1") (pin "16") (pinfunction "I/O(16)_16") (pintype "bidirectional"))
    )
    (net (code "55") (name "Net-(U1-I{slash}O(17))") (class "Default")
      (node (ref "R1") (pin "2") (pinfunction "2_2") (pintype "unspecified"))
      (node (ref "U1") (pin "17") (pinfunction "I/O(17)_17") (pintype "bidirectional"))
    )
    (net (code "56") (name "Net-(U1-I{slash}O(19))") (class "Default")
      (node (ref "PD2") (pin "1") (pinfunction "1_1") (pintype "unspecified"))
      (node (ref "U1") (pin "19") (pinfunction "I/O(19)_19") (pintype "bidirectional"))
    )
    (net (code "57") (name "Net-(U2-IN1)") (class "Default")
      (node (ref "C11") (pin "2") (pinfunction "2_2") (pintype "input"))
      (node (ref "R1") (pin "1") (pinfunction "1_1") (pintype "unspecified"))
      (node (ref "R7") (pin "2") (pinfunction "2_2") (pintype "input"))
      (node (ref "R|4") (pin "1") (pinfunction "1_1") (pintype "unspecified"))
      (node (ref "U2") (pin "1") (pinfunction "IN1_1") (pintype "unspecified"))
    )
    (net (code "58") (name "Net-(U2-IN2)") (class "Default")
      (node (ref "C12") (pin "2") (pinfunction "2_2") (pintype "input"))
      (node (ref "R2") (pin "1") (pinfunction "1_1") (pintype "unspecified"))
      (node (ref "R8") (pin "2") (pinfunction "2_2") (pintype "input"))
      (node (ref "R|5") (pin "1") (pinfunction "1_1") (pintype "unspecified"))
      (node (ref "U2") (pin "2") (pinfunction "IN2_2") (pintype "unspecified"))
    )
    (net (code "59") (name "Net-(U2-IN3)") (class "Default")
      (node (ref "C13") (pin "2") (pinfunction "2_2") (pintype "input"))
      (node (ref "R3") (pin "1") (pinfunction "1_1") (pintype "unspecified"))
      (node (ref "R9") (pin "2") (pinfunction "2_2") (pintype "input"))
      (node (ref "R|6") (pin "1") (pinfunction "1_1") (pintype "unspecified"))
      (node (ref "U2") (pin "3") (pinfunction "IN3_3") (pintype "unspecified"))
    )
    (net (code "60") (name "Net-(U2-OUT1)") (class "Default")
      (node (ref "R10") (pin "2") (pinfunction "2_2") (pintype "input"))
      (node (ref "U2") (pin "8") (pinfunction "OUT1_8") (pintype "unspecified"))
    )
    (net (code "61") (name "Net-(U2-OUT2)") (class "Default")
      (node (ref "R11") (pin "2") (pinfunction "2_2") (pintype "input"))
      (node (ref "U2") (pin "7") (pinfunction "OUT2_7") (pintype "unspecified"))
    )
    (net (code "62") (name "Net-(U2-OUT3)") (class "Default")
      (node (ref "R12") (pin "2") (pinfunction "2_2") (pintype "input"))
      (node (ref "U2") (pin "6") (pinfunction "OUT3_6") (pintype "unspecified"))
    )
    (net (code "63") (name "Net-(U4-NO1)") (class "Default")
      (node (ref "R17") (pin "1") (pinfunction "1_1") (pintype "input"))
      (node (ref "U4") (pin "2") (pinfunction "NO1_2") (pintype "unspecified"))
    )
    (net (code "64") (name "Net-(U5-NO2)") (class "Default")
      (node (ref "R16") (pin "1") (pinfunction "1_1") (pintype "input"))
      (node (ref "U5") (pin "10") (pinfunction "NO2_10") (pintype "unspecified"))
    )
    (net (code "65") (name "Net-(U6-COM1)") (class "Default")
      (node (ref "RLED2") (pin "1") (pinfunction "1_1") (pintype "unspecified"))
      (node (ref "U6") (pin "3") (pinfunction "COM1_3") (pintype "unspecified"))
    )
    (net (code "66") (name "Net-(U6-COM2)") (class "Default")
      (node (ref "RLED3") (pin "2") (pinfunction "2_2") (pintype "unspecified"))
      (node (ref "U6") (pin "9") (pinfunction "COM2_9") (pintype "unspecified"))
    )
    (net (code "67") (name "Net-(U8-IN{slash}A)") (class "Default")
      (node (ref "C9") (pin "2") (pinfunction "2_2") (pintype "unspecified"))
      (node (ref "R21") (pin "1") (pinfunction "1_1") (pintype "unspecified"))
      (node (ref "R|21") (pin "1") (pinfunction "1_1") (pintype "unspecified"))
      (node (ref "U8") (pin "2") (pinfunction "IN/A_2") (pintype "unspecified"))
    )
    (net (code "68") (name "RED") (class "Default")
      (node (ref "R10") (pin "1") (pinfunction "1_1") (pintype "input"))
      (node (ref "U4") (pin "10") (pinfunction "NO2_10") (pintype "unspecified"))
    )
    (net (code "69") (name "RED+CHROMA") (class "Default")
      (node (ref "U4") (pin "9") (pinfunction "COM2_9") (pintype "unspecified"))
      (node (ref "X3") (pin "15") (pinfunction "15_15") (pintype "bidirectional"))
    )
    (net (code "70") (name "R_TTL") (class "Default")
      (node (ref "U1") (pin "5") (pinfunction "I4(5)_5") (pintype "bidirectional"))
      (node (ref "X1") (pin "3") (pinfunction "3_3") (pintype "bidirectional"))
    )
    (net (code "71") (name "SYNC") (class "Default")
      (node (ref "U5") (pin "2") (pinfunction "NO1_2") (pintype "unspecified"))
      (node (ref "U5") (pin "9") (pinfunction "COM2_9") (pintype "unspecified"))
    )
    (net (code "72") (name "SYNC_MODE") (class "Default")
      (node (ref "DIP1") (pin "3") (pinfunction "3_3") (pintype "unspecified"))
      (node (ref "R26") (pin "1") (pinfunction "1_1") (pintype "unspecified"))
      (node (ref "U5") (pin "8") (pinfunction "IN2_8") (pintype "unspecified"))
      (node (ref "U6") (pin "8") (pinfunction "IN2_8") (pintype "unspecified"))
    )
    (net (code "73") (name "VCC") (class "Default")
      (node (ref "C1") (pin "2") (pinfunction "2_2") (pintype "unspecified"))
      (node (ref "C2") (pin "1") (pinfunction "1_1") (pintype "unspecified"))
      (node (ref "C3") (pin "1") (pinfunction "1_1") (pintype "unspecified"))
      (node (ref "C4") (pin "1") (pinfunction "1_1") (pintype "unspecified"))
      (node (ref "C5") (pin "1") (pinfunction "1_1") (pintype "unspecified"))
      (node (ref "C6") (pin "1") (pinfunction "1_1") (pintype "unspecified"))
      (node (ref "C7") (pin "2") (pinfunction "2_2") (pintype "unspecified"))
      (node (ref "C8") (pin "2") (pinfunction "2_2") (pintype "unspecified"))
      (node (ref "C|2") (pin "1") (pinfunction "1_1") (pintype "unspecified"))
      (node (ref "D1") (pin "1") (pinfunction "K_1") (pintype "unspecified"))
      (node (ref "DIP1") (pin "1") (pinfunction "1_1") (pintype "unspecified"))
      (node (ref "DIP1") (pin "2") (pinfunction "2_2") (pintype "unspecified"))
      (node (ref "L1") (pin "2") (pinfunction "2_2") (pintype "unspecified"))
      (node (ref "L2") (pin "1") (pinfunction "1_1") (pintype "unspecified"))
      (node (ref "R17") (pin "2") (pinfunction "2_2") (pintype "input"))
      (node (ref "R20") (pin "2") (pinfunction "2_2") (pintype "unspecified"))
      (node (ref "RLED2") (pin "2") (pinfunction "2_2") (pintype "unspecified"))
      (node (ref "RLED3") (pin "1") (pinfunction "1_1") (pintype "unspecified"))
      (node (ref "R|18") (pin "1") (pinfunction "1_1") (pintype "unspecified"))
      (node (ref "R|20") (pin "2") (pinfunction "2_2") (pintype "unspecified"))
      (node (ref "U1") (pin "20") (pinfunction "VCC(20)_20") (pintype "bidirectional"))
      (node (ref "U2") (pin "4") (pinfunction "VCC_4") (pintype "unspecified"))
      (node (ref "U3") (pin "1") (pinfunction "V+_1") (pintype "unspecified"))
      (node (ref "U4") (pin "1") (pinfunction "V+_1") (pintype "unspecified"))
      (node (ref "U5") (pin "1") (pinfunction "V+_1") (pintype "unspecified"))
      (node (ref "U6") (pin "1") (pinfunction "V+_1") (pintype "unspecified"))
      (node (ref "U7") (pin "10") (pinfunction "SET2_10") (pintype "unspecified"))
      (node (ref "U7") (pin "11") (pinfunction "J2_11") (pintype "unspecified"))
      (node (ref "U7") (pin "12") (pinfunction "K2_12") (pintype "unspecified"))
      (node (ref "U7") (pin "16") (pinfunction "VCC_16") (pintype "unspecified"))
      (node (ref "U7") (pin "2") (pinfunction "K1_2") (pintype "unspecified"))
      (node (ref "U7") (pin "3") (pinfunction "J1_3") (pintype "unspecified"))
      (node (ref "U7") (pin "4") (pinfunction "SET1_4") (pintype "unspecified"))
      (node (ref "U8") (pin "5") (pinfunction "VCC_5") (pintype "unspecified"))
    )
    (net (code "74") (name "VCC_C128") (class "Default")
      (node (ref "C19") (pin "1") (pinfunction "1_1") (pintype "input"))
      (node (ref "L2") (pin "2") (pinfunction "2_2") (pintype "unspecified"))
      (node (ref "X2") (pin "8") (pinfunction "8_8") (pintype "bidirectional"))
    )
    (net (code "75") (name "VIDEO_MODE") (class "Default")
      (node (ref "DIP1") (pin "4") (pinfunction "4_4") (pintype "unspecified"))
      (node (ref "R24") (pin "1") (pinfunction "1_1") (pintype "unspecified"))
      (node (ref "U3") (pin "4") (pinfunction "IN1_4") (pintype "unspecified"))
      (node (ref "U3") (pin "8") (pinfunction "IN2_8") (pintype "unspecified"))
      (node (ref "U6") (pin "4") (pinfunction "IN1_4") (pintype "unspecified"))
    )
    (net (code "76") (name "VSYNC") (class "Default")
      (node (ref "U1") (pin "7") (pinfunction "I6(7)_7") (pintype "bidirectional"))
      (node (ref "X1") (pin "9") (pinfunction "9_9") (pintype "bidirectional"))
    )
    (net (code "77") (name "unconnected-(LED1-R-Pad3)") (class "Default")
      (node (ref "LED1") (pin "3") (pinfunction "R_3") (pintype "unspecified+no_connect"))
    )
    (net (code "78") (name "unconnected-(LED2-B-Pad2)") (class "Default")
      (node (ref "LED2") (pin "2") (pinfunction "B_2") (pintype "unspecified+no_connect"))
    )
    (net (code "79") (name "unconnected-(LED3-B-Pad2)") (class "Default")
      (node (ref "LED3") (pin "2") (pinfunction "B_2") (pintype "unspecified+no_connect"))
    )
    (net (code "80") (name "unconnected-(U7-#Q2-Pad7)") (class "Default")
      (node (ref "U7") (pin "7") (pinfunction "#Q2_7") (pintype "unspecified+no_connect"))
    )
    (net (code "81") (name "unconnected-(U8-NC-Pad1)") (class "Default")
      (node (ref "U8") (pin "1") (pinfunction "NC_1") (pintype "unspecified+no_connect"))
    )
    (net (code "82") (name "unconnected-(X2-Pad7)") (class "Default")
      (node (ref "X2") (pin "7") (pinfunction "7_7") (pintype "bidirectional+no_connect"))
    )
    (net (code "83") (name "unconnected-(X3-Pad2)") (class "Default")
      (node (ref "X3") (pin "2") (pinfunction "2_2") (pintype "bidirectional+no_connect"))
    )
    (net (code "84") (name "unconnected-(X3-Pad6)") (class "Default")
      (node (ref "X3") (pin "6") (pinfunction "6_6") (pintype "bidirectional+no_connect"))
    )
    (net (code "85") (name "unconnected-(X3-Pad8)") (class "Default")
      (node (ref "X3") (pin "8") (pinfunction "8_8") (pintype "bidirectional+no_connect"))
    )
    (net (code "86") (name "unconnected-(X3-Pad10)") (class "Default")
      (node (ref "X3") (pin "10") (pinfunction "10_10") (pintype "bidirectional+no_connect"))
    )
    (net (code "87") (name "unconnected-(X3-Pad12)") (class "Default")
      (node (ref "X3") (pin "12") (pinfunction "12_12") (pintype "bidirectional+no_connect"))
    )
    (net (code "88") (name "unconnected-(X3-Pad20)") (class "Default")
      (node (ref "X3") (pin "20") (pinfunction "20_20") (pintype "bidirectional+no_connect"))
    )
  )
)
